# schem.net
KiCad netlist of a schematic drawn in EAGLE
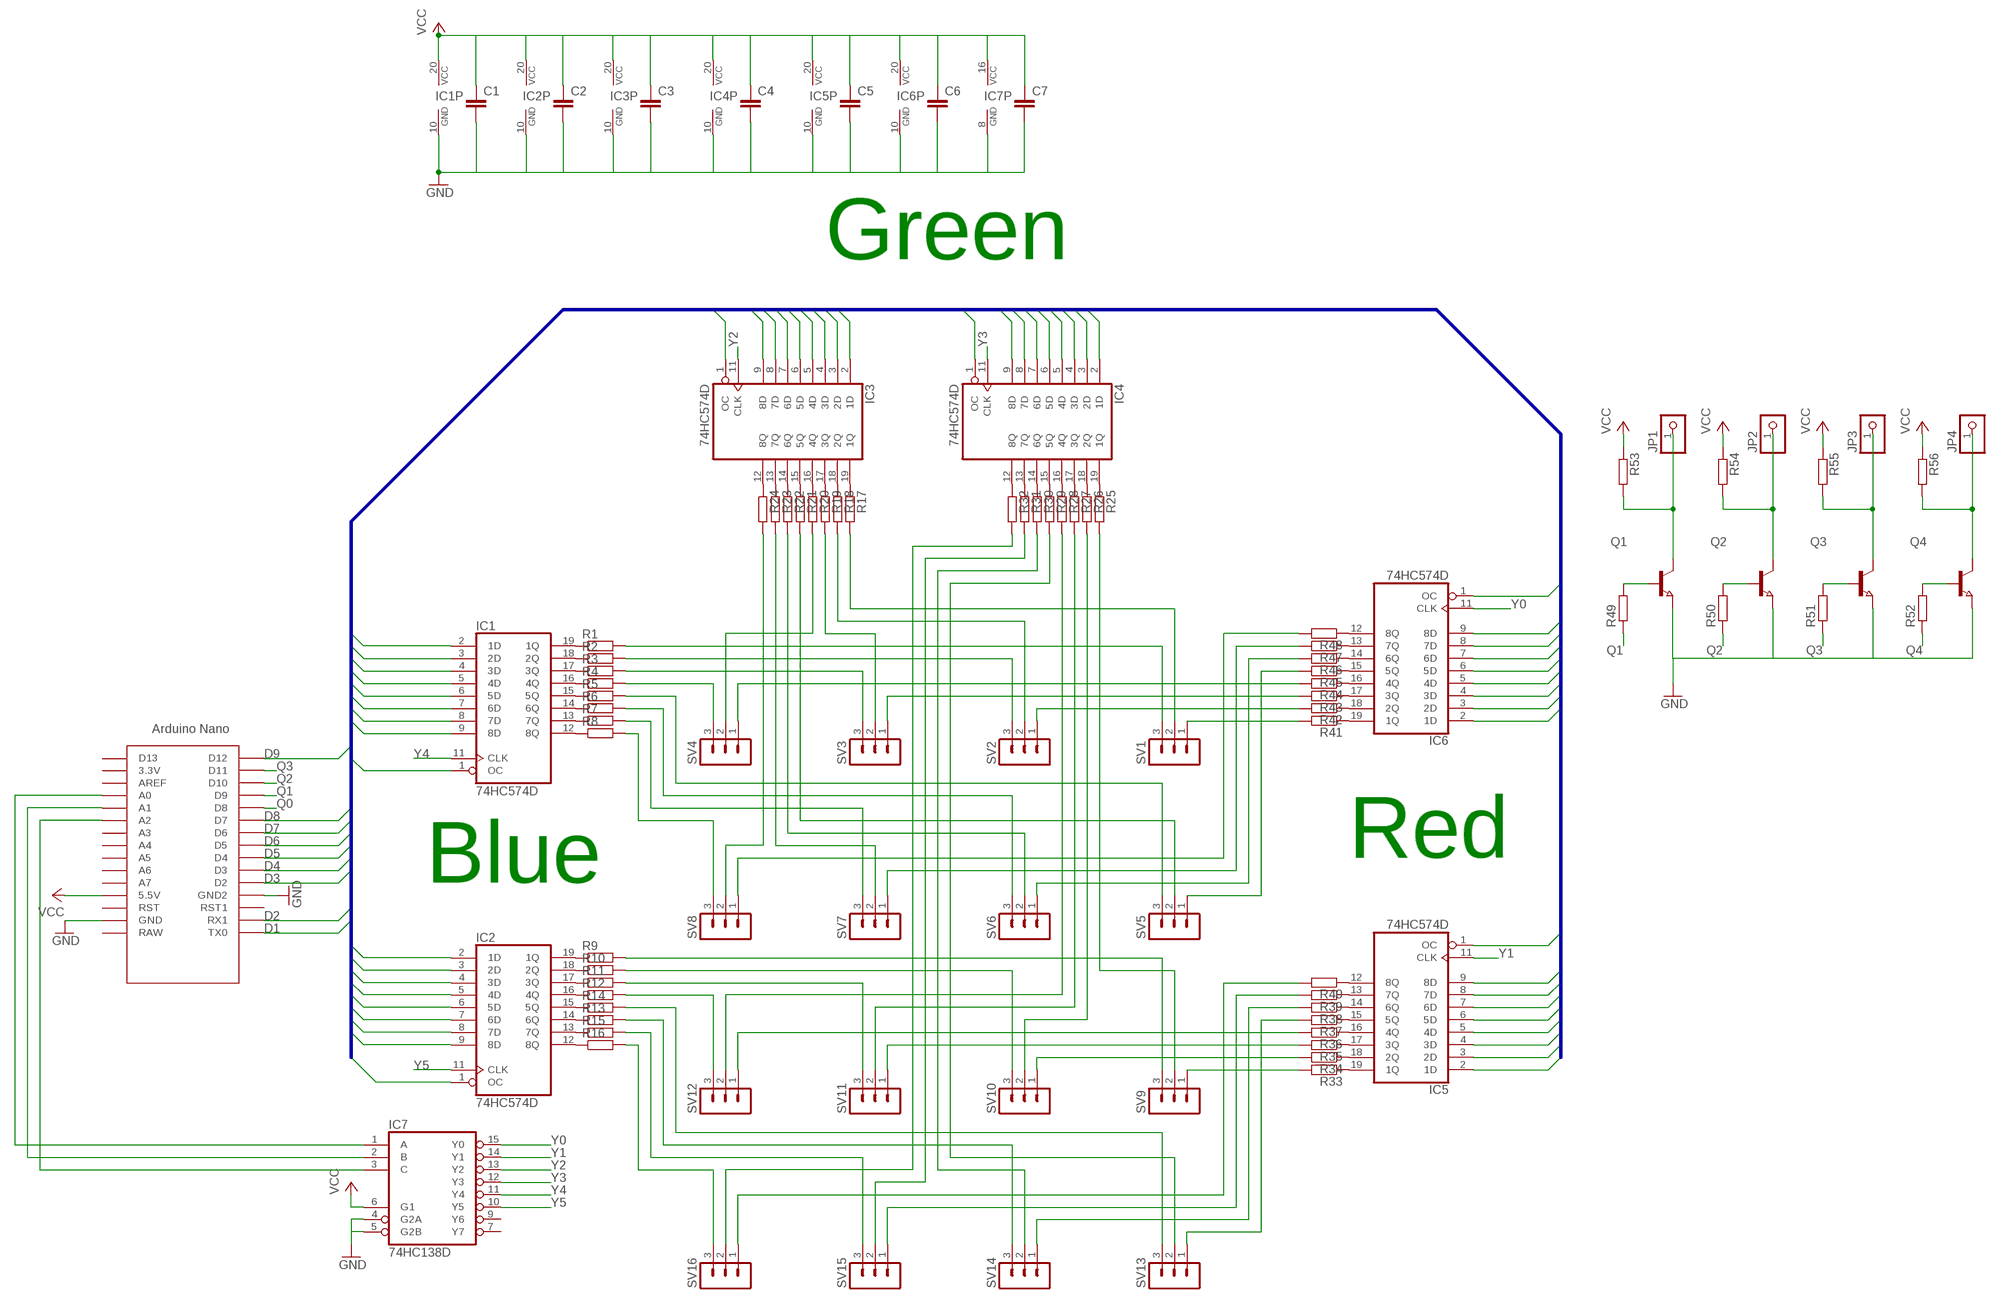
[diagram p0: schematic, sheet 1]

(export (version "E")
  (design (tool "Eeschema 10.0.6"))
  (components
    (comp (ref "C1")
      (value "C-EUC0805")
      (footprint "eagle-import:C0805")
      (libsource (lib "eagle-import") (part "C-EUC0805"))
    )
    (comp (ref "C2")
      (value "C-EUC0805")
      (footprint "eagle-import:C0805")
      (libsource (lib "eagle-import") (part "C-EUC0805"))
    )
    (comp (ref "C3")
      (value "C-EUC0805")
      (footprint "eagle-import:C0805")
      (libsource (lib "eagle-import") (part "C-EUC0805"))
    )
    (comp (ref "C4")
      (value "C-EUC0805")
      (footprint "eagle-import:C0805")
      (libsource (lib "eagle-import") (part "C-EUC0805"))
    )
    (comp (ref "C5")
      (value "C-EUC0805")
      (footprint "eagle-import:C0805")
      (libsource (lib "eagle-import") (part "C-EUC0805"))
    )
    (comp (ref "C6")
      (value "C-EUC0805")
      (footprint "eagle-import:C0805")
      (libsource (lib "eagle-import") (part "C-EUC0805"))
    )
    (comp (ref "C7")
      (value "C-EUC0805")
      (footprint "eagle-import:C0805")
      (libsource (lib "eagle-import") (part "C-EUC0805"))
    )
    (comp (ref "IC1")
      (value "74HC574D")
      (footprint "eagle-import:SO20W")
      (libsource (lib "eagle-import") (part "74574DHC"))
    )
    (comp (ref "IC2")
      (value "74HC574D")
      (footprint "eagle-import:SO20W")
      (libsource (lib "eagle-import") (part "74574DHC"))
    )
    (comp (ref "IC3")
      (value "74HC574D")
      (footprint "eagle-import:SO20W")
      (libsource (lib "eagle-import") (part "74574DHC"))
    )
    (comp (ref "IC4")
      (value "74HC574D")
      (footprint "eagle-import:SO20W")
      (libsource (lib "eagle-import") (part "74574DHC"))
    )
    (comp (ref "IC5")
      (value "74HC574D")
      (footprint "eagle-import:SO20W")
      (libsource (lib "eagle-import") (part "74574DHC"))
    )
    (comp (ref "IC6")
      (value "74HC574D")
      (footprint "eagle-import:SO20W")
      (libsource (lib "eagle-import") (part "74574DHC"))
    )
    (comp (ref "IC7")
      (value "74HC138D")
      (footprint "eagle-import:SO16")
      (libsource (lib "eagle-import") (part "74138DHC"))
    )
    (comp (ref "JP1")
      (value "PINHD-1X1")
      (footprint "eagle-import:1X01")
      (libsource (lib "eagle-import") (part "PINHD-1X1"))
    )
    (comp (ref "JP2")
      (value "PINHD-1X1")
      (footprint "eagle-import:1X01")
      (libsource (lib "eagle-import") (part "PINHD-1X1"))
    )
    (comp (ref "JP3")
      (value "PINHD-1X1")
      (footprint "eagle-import:1X01")
      (libsource (lib "eagle-import") (part "PINHD-1X1"))
    )
    (comp (ref "JP4")
      (value "PINHD-1X1")
      (footprint "eagle-import:1X01")
      (libsource (lib "eagle-import") (part "PINHD-1X1"))
    )
    (comp (ref "Q1")
      (value "NPN-TRANSISTOR_SOT23")
      (footprint "eagle-import:SOT23")
      (libsource (lib "eagle-import") (part "NPN-TRANSISTOR_SOT23"))
    )
    (comp (ref "Q2")
      (value "NPN-TRANSISTOR_SOT23")
      (footprint "eagle-import:SOT23")
      (libsource (lib "eagle-import") (part "NPN-TRANSISTOR_SOT23"))
    )
    (comp (ref "Q3")
      (value "NPN-TRANSISTOR_SOT23")
      (footprint "eagle-import:SOT23")
      (libsource (lib "eagle-import") (part "NPN-TRANSISTOR_SOT23"))
    )
    (comp (ref "Q4")
      (value "NPN-TRANSISTOR_SOT23")
      (footprint "eagle-import:SOT23")
      (libsource (lib "eagle-import") (part "NPN-TRANSISTOR_SOT23"))
    )
    (comp (ref "R1")
      (value "R-EU_R0805")
      (footprint "eagle-import:R0805")
      (libsource (lib "eagle-import") (part "R-EU_R0805"))
    )
    (comp (ref "R2")
      (value "R-EU_R0805")
      (footprint "eagle-import:R0805")
      (libsource (lib "eagle-import") (part "R-EU_R0805"))
    )
    (comp (ref "R3")
      (value "R-EU_R0805")
      (footprint "eagle-import:R0805")
      (libsource (lib "eagle-import") (part "R-EU_R0805"))
    )
    (comp (ref "R4")
      (value "R-EU_R0805")
      (footprint "eagle-import:R0805")
      (libsource (lib "eagle-import") (part "R-EU_R0805"))
    )
    (comp (ref "R5")
      (value "R-EU_R0805")
      (footprint "eagle-import:R0805")
      (libsource (lib "eagle-import") (part "R-EU_R0805"))
    )
    (comp (ref "R6")
      (value "R-EU_R0805")
      (footprint "eagle-import:R0805")
      (libsource (lib "eagle-import") (part "R-EU_R0805"))
    )
    (comp (ref "R7")
      (value "R-EU_R0805")
      (footprint "eagle-import:R0805")
      (libsource (lib "eagle-import") (part "R-EU_R0805"))
    )
    (comp (ref "R8")
      (value "R-EU_R0805")
      (footprint "eagle-import:R0805")
      (libsource (lib "eagle-import") (part "R-EU_R0805"))
    )
    (comp (ref "R9")
      (value "R-EU_R0805")
      (footprint "eagle-import:R0805")
      (libsource (lib "eagle-import") (part "R-EU_R0805"))
    )
    (comp (ref "R10")
      (value "R-EU_R0805")
      (footprint "eagle-import:R0805")
      (libsource (lib "eagle-import") (part "R-EU_R0805"))
    )
    (comp (ref "R11")
      (value "R-EU_R0805")
      (footprint "eagle-import:R0805")
      (libsource (lib "eagle-import") (part "R-EU_R0805"))
    )
    (comp (ref "R12")
      (value "R-EU_R0805")
      (footprint "eagle-import:R0805")
      (libsource (lib "eagle-import") (part "R-EU_R0805"))
    )
    (comp (ref "R13")
      (value "R-EU_R0805")
      (footprint "eagle-import:R0805")
      (libsource (lib "eagle-import") (part "R-EU_R0805"))
    )
    (comp (ref "R14")
      (value "R-EU_R0805")
      (footprint "eagle-import:R0805")
      (libsource (lib "eagle-import") (part "R-EU_R0805"))
    )
    (comp (ref "R15")
      (value "R-EU_R0805")
      (footprint "eagle-import:R0805")
      (libsource (lib "eagle-import") (part "R-EU_R0805"))
    )
    (comp (ref "R16")
      (value "R-EU_R0805")
      (footprint "eagle-import:R0805")
      (libsource (lib "eagle-import") (part "R-EU_R0805"))
    )
    (comp (ref "R17")
      (value "R-EU_R0805")
      (footprint "eagle-import:R0805")
      (libsource (lib "eagle-import") (part "R-EU_R0805"))
    )
    (comp (ref "R18")
      (value "R-EU_R0805")
      (footprint "eagle-import:R0805")
      (libsource (lib "eagle-import") (part "R-EU_R0805"))
    )
    (comp (ref "R19")
      (value "R-EU_R0805")
      (footprint "eagle-import:R0805")
      (libsource (lib "eagle-import") (part "R-EU_R0805"))
    )
    (comp (ref "R20")
      (value "R-EU_R0805")
      (footprint "eagle-import:R0805")
      (libsource (lib "eagle-import") (part "R-EU_R0805"))
    )
    (comp (ref "R21")
      (value "R-EU_R0805")
      (footprint "eagle-import:R0805")
      (libsource (lib "eagle-import") (part "R-EU_R0805"))
    )
    (comp (ref "R22")
      (value "R-EU_R0805")
      (footprint "eagle-import:R0805")
      (libsource (lib "eagle-import") (part "R-EU_R0805"))
    )
    (comp (ref "R23")
      (value "R-EU_R0805")
      (footprint "eagle-import:R0805")
      (libsource (lib "eagle-import") (part "R-EU_R0805"))
    )
    (comp (ref "R24")
      (value "R-EU_R0805")
      (footprint "eagle-import:R0805")
      (libsource (lib "eagle-import") (part "R-EU_R0805"))
    )
    (comp (ref "R25")
      (value "R-EU_R0805")
      (footprint "eagle-import:R0805")
      (libsource (lib "eagle-import") (part "R-EU_R0805"))
    )
    (comp (ref "R26")
      (value "R-EU_R0805")
      (footprint "eagle-import:R0805")
      (libsource (lib "eagle-import") (part "R-EU_R0805"))
    )
    (comp (ref "R27")
      (value "R-EU_R0805")
      (footprint "eagle-import:R0805")
      (libsource (lib "eagle-import") (part "R-EU_R0805"))
    )
    (comp (ref "R28")
      (value "R-EU_R0805")
      (footprint "eagle-import:R0805")
      (libsource (lib "eagle-import") (part "R-EU_R0805"))
    )
    (comp (ref "R29")
      (value "R-EU_R0805")
      (footprint "eagle-import:R0805")
      (libsource (lib "eagle-import") (part "R-EU_R0805"))
    )
    (comp (ref "R30")
      (value "R-EU_R0805")
      (footprint "eagle-import:R0805")
      (libsource (lib "eagle-import") (part "R-EU_R0805"))
    )
    (comp (ref "R31")
      (value "R-EU_R0805")
      (footprint "eagle-import:R0805")
      (libsource (lib "eagle-import") (part "R-EU_R0805"))
    )
    (comp (ref "R32")
      (value "R-EU_R0805")
      (footprint "eagle-import:R0805")
      (libsource (lib "eagle-import") (part "R-EU_R0805"))
    )
    (comp (ref "R33")
      (value "R-EU_R0805")
      (footprint "eagle-import:R0805")
      (libsource (lib "eagle-import") (part "R-EU_R0805"))
    )
    (comp (ref "R34")
      (value "R-EU_R0805")
      (footprint "eagle-import:R0805")
      (libsource (lib "eagle-import") (part "R-EU_R0805"))
    )
    (comp (ref "R35")
      (value "R-EU_R0805")
      (footprint "eagle-import:R0805")
      (libsource (lib "eagle-import") (part "R-EU_R0805"))
    )
    (comp (ref "R36")
      (value "R-EU_R0805")
      (footprint "eagle-import:R0805")
      (libsource (lib "eagle-import") (part "R-EU_R0805"))
    )
    (comp (ref "R37")
      (value "R-EU_R0805")
      (footprint "eagle-import:R0805")
      (libsource (lib "eagle-import") (part "R-EU_R0805"))
    )
    (comp (ref "R38")
      (value "R-EU_R0805")
      (footprint "eagle-import:R0805")
      (libsource (lib "eagle-import") (part "R-EU_R0805"))
    )
    (comp (ref "R39")
      (value "R-EU_R0805")
      (footprint "eagle-import:R0805")
      (libsource (lib "eagle-import") (part "R-EU_R0805"))
    )
    (comp (ref "R40")
      (value "R-EU_R0805")
      (footprint "eagle-import:R0805")
      (libsource (lib "eagle-import") (part "R-EU_R0805"))
    )
    (comp (ref "R41")
      (value "R-EU_R0805")
      (footprint "eagle-import:R0805")
      (libsource (lib "eagle-import") (part "R-EU_R0805"))
    )
    (comp (ref "R42")
      (value "R-EU_R0805")
      (footprint "eagle-import:R0805")
      (libsource (lib "eagle-import") (part "R-EU_R0805"))
    )
    (comp (ref "R43")
      (value "R-EU_R0805")
      (footprint "eagle-import:R0805")
      (libsource (lib "eagle-import") (part "R-EU_R0805"))
    )
    (comp (ref "R44")
      (value "R-EU_R0805")
      (footprint "eagle-import:R0805")
      (libsource (lib "eagle-import") (part "R-EU_R0805"))
    )
    (comp (ref "R45")
      (value "R-EU_R0805")
      (footprint "eagle-import:R0805")
      (libsource (lib "eagle-import") (part "R-EU_R0805"))
    )
    (comp (ref "R46")
      (value "R-EU_R0805")
      (footprint "eagle-import:R0805")
      (libsource (lib "eagle-import") (part "R-EU_R0805"))
    )
    (comp (ref "R47")
      (value "R-EU_R0805")
      (footprint "eagle-import:R0805")
      (libsource (lib "eagle-import") (part "R-EU_R0805"))
    )
    (comp (ref "R48")
      (value "R-EU_R0805")
      (footprint "eagle-import:R0805")
      (libsource (lib "eagle-import") (part "R-EU_R0805"))
    )
    (comp (ref "R49")
      (value "R-EU_R0805")
      (footprint "eagle-import:R0805")
      (libsource (lib "eagle-import") (part "R-EU_R0805"))
    )
    (comp (ref "R50")
      (value "R-EU_R0805")
      (footprint "eagle-import:R0805")
      (libsource (lib "eagle-import") (part "R-EU_R0805"))
    )
    (comp (ref "R51")
      (value "R-EU_R0805")
      (footprint "eagle-import:R0805")
      (libsource (lib "eagle-import") (part "R-EU_R0805"))
    )
    (comp (ref "R52")
      (value "R-EU_R0805")
      (footprint "eagle-import:R0805")
      (libsource (lib "eagle-import") (part "R-EU_R0805"))
    )
    (comp (ref "R53")
      (value "R-EU_R0805")
      (footprint "eagle-import:R0805")
      (libsource (lib "eagle-import") (part "R-EU_R0805"))
    )
    (comp (ref "R54")
      (value "R-EU_R0805")
      (footprint "eagle-import:R0805")
      (libsource (lib "eagle-import") (part "R-EU_R0805"))
    )
    (comp (ref "R55")
      (value "R-EU_R0805")
      (footprint "eagle-import:R0805")
      (libsource (lib "eagle-import") (part "R-EU_R0805"))
    )
    (comp (ref "R56")
      (value "R-EU_R0805")
      (footprint "eagle-import:R0805")
      (libsource (lib "eagle-import") (part "R-EU_R0805"))
    )
    (comp (ref "SV1")
      (value "MA03-1")
      (footprint "eagle-import:MA03-1")
      (libsource (lib "eagle-import") (part "MA03-1"))
    )
    (comp (ref "SV2")
      (value "MA03-1")
      (footprint "eagle-import:MA03-1")
      (libsource (lib "eagle-import") (part "MA03-1"))
    )
    (comp (ref "SV3")
      (value "MA03-1")
      (footprint "eagle-import:MA03-1")
      (libsource (lib "eagle-import") (part "MA03-1"))
    )
    (comp (ref "SV4")
      (value "MA03-1")
      (footprint "eagle-import:MA03-1")
      (libsource (lib "eagle-import") (part "MA03-1"))
    )
    (comp (ref "SV5")
      (value "MA03-1")
      (footprint "eagle-import:MA03-1")
      (libsource (lib "eagle-import") (part "MA03-1"))
    )
    (comp (ref "SV6")
      (value "MA03-1")
      (footprint "eagle-import:MA03-1")
      (libsource (lib "eagle-import") (part "MA03-1"))
    )
    (comp (ref "SV7")
      (value "MA03-1")
      (footprint "eagle-import:MA03-1")
      (libsource (lib "eagle-import") (part "MA03-1"))
    )
    (comp (ref "SV8")
      (value "MA03-1")
      (footprint "eagle-import:MA03-1")
      (libsource (lib "eagle-import") (part "MA03-1"))
    )
    (comp (ref "SV9")
      (value "MA03-1")
      (footprint "eagle-import:MA03-1")
      (libsource (lib "eagle-import") (part "MA03-1"))
    )
    (comp (ref "SV10")
      (value "MA03-1")
      (footprint "eagle-import:MA03-1")
      (libsource (lib "eagle-import") (part "MA03-1"))
    )
    (comp (ref "SV11")
      (value "MA03-1")
      (footprint "eagle-import:MA03-1")
      (libsource (lib "eagle-import") (part "MA03-1"))
    )
    (comp (ref "SV12")
      (value "MA03-1")
      (footprint "eagle-import:MA03-1")
      (libsource (lib "eagle-import") (part "MA03-1"))
    )
    (comp (ref "SV13")
      (value "MA03-1")
      (footprint "eagle-import:MA03-1")
      (libsource (lib "eagle-import") (part "MA03-1"))
    )
    (comp (ref "SV14")
      (value "MA03-1")
      (footprint "eagle-import:MA03-1")
      (libsource (lib "eagle-import") (part "MA03-1"))
    )
    (comp (ref "SV15")
      (value "MA03-1")
      (footprint "eagle-import:MA03-1")
      (libsource (lib "eagle-import") (part "MA03-1"))
    )
    (comp (ref "SV16")
      (value "MA03-1")
      (footprint "eagle-import:MA03-1")
      (libsource (lib "eagle-import") (part "MA03-1"))
    )
    (comp (ref "U$1")
      (value "NANO")
      (footprint "eagle-import:NANO")
      (libsource (lib "eagle-import") (part "NANO"))
    )
  )
  (nets
    (net (code "1") (name "/D1") (class "Default")
      (node (ref "IC1") (pin "2") (pinfunction "1D_2") (pintype "input"))
      (node (ref "IC2") (pin "2") (pinfunction "1D_2") (pintype "input"))
      (node (ref "IC3") (pin "2") (pinfunction "1D_2") (pintype "input"))
      (node (ref "IC4") (pin "2") (pinfunction "1D_2") (pintype "input"))
      (node (ref "IC5") (pin "2") (pinfunction "1D_2") (pintype "input"))
      (node (ref "IC6") (pin "2") (pinfunction "1D_2") (pintype "input"))
      (node (ref "U$1") (pin "TX0") (pinfunction "TX0_TX0") (pintype "bidirectional"))
    )
    (net (code "2") (name "/D2") (class "Default")
      (node (ref "IC1") (pin "3") (pinfunction "2D_3") (pintype "input"))
      (node (ref "IC2") (pin "3") (pinfunction "2D_3") (pintype "input"))
      (node (ref "IC3") (pin "3") (pinfunction "2D_3") (pintype "input"))
      (node (ref "IC4") (pin "3") (pinfunction "2D_3") (pintype "input"))
      (node (ref "IC5") (pin "3") (pinfunction "2D_3") (pintype "input"))
      (node (ref "IC6") (pin "3") (pinfunction "2D_3") (pintype "input"))
      (node (ref "U$1") (pin "RX1") (pinfunction "RX1_RX1") (pintype "bidirectional"))
    )
    (net (code "3") (name "/D3") (class "Default")
      (node (ref "IC1") (pin "4") (pinfunction "3D_4") (pintype "input"))
      (node (ref "IC2") (pin "4") (pinfunction "3D_4") (pintype "input"))
      (node (ref "IC3") (pin "4") (pinfunction "3D_4") (pintype "input"))
      (node (ref "IC4") (pin "4") (pinfunction "3D_4") (pintype "input"))
      (node (ref "IC5") (pin "4") (pinfunction "3D_4") (pintype "input"))
      (node (ref "IC6") (pin "4") (pinfunction "3D_4") (pintype "input"))
      (node (ref "U$1") (pin "D2") (pinfunction "D2_D2") (pintype "bidirectional"))
    )
    (net (code "4") (name "/D4") (class "Default")
      (node (ref "IC1") (pin "5") (pinfunction "4D_5") (pintype "input"))
      (node (ref "IC2") (pin "5") (pinfunction "4D_5") (pintype "input"))
      (node (ref "IC3") (pin "5") (pinfunction "4D_5") (pintype "input"))
      (node (ref "IC4") (pin "5") (pinfunction "4D_5") (pintype "input"))
      (node (ref "IC5") (pin "5") (pinfunction "4D_5") (pintype "input"))
      (node (ref "IC6") (pin "5") (pinfunction "4D_5") (pintype "input"))
      (node (ref "U$1") (pin "D3") (pinfunction "D3_D3") (pintype "bidirectional"))
    )
    (net (code "5") (name "/D5") (class "Default")
      (node (ref "IC1") (pin "6") (pinfunction "5D_6") (pintype "input"))
      (node (ref "IC2") (pin "6") (pinfunction "5D_6") (pintype "input"))
      (node (ref "IC3") (pin "6") (pinfunction "5D_6") (pintype "input"))
      (node (ref "IC4") (pin "6") (pinfunction "5D_6") (pintype "input"))
      (node (ref "IC5") (pin "6") (pinfunction "5D_6") (pintype "input"))
      (node (ref "IC6") (pin "6") (pinfunction "5D_6") (pintype "input"))
      (node (ref "U$1") (pin "D4") (pinfunction "D4_D4") (pintype "bidirectional"))
    )
    (net (code "6") (name "/D6") (class "Default")
      (node (ref "IC1") (pin "7") (pinfunction "6D_7") (pintype "input"))
      (node (ref "IC2") (pin "7") (pinfunction "6D_7") (pintype "input"))
      (node (ref "IC3") (pin "7") (pinfunction "6D_7") (pintype "input"))
      (node (ref "IC4") (pin "7") (pinfunction "6D_7") (pintype "input"))
      (node (ref "IC5") (pin "7") (pinfunction "6D_7") (pintype "input"))
      (node (ref "IC6") (pin "7") (pinfunction "6D_7") (pintype "input"))
      (node (ref "U$1") (pin "D5") (pinfunction "D5_D5") (pintype "bidirectional"))
    )
    (net (code "7") (name "/D7") (class "Default")
      (node (ref "IC1") (pin "8") (pinfunction "7D_8") (pintype "input"))
      (node (ref "IC2") (pin "8") (pinfunction "7D_8") (pintype "input"))
      (node (ref "IC3") (pin "8") (pinfunction "7D_8") (pintype "input"))
      (node (ref "IC4") (pin "8") (pinfunction "7D_8") (pintype "input"))
      (node (ref "IC5") (pin "8") (pinfunction "7D_8") (pintype "input"))
      (node (ref "IC6") (pin "8") (pinfunction "7D_8") (pintype "input"))
      (node (ref "U$1") (pin "D6") (pinfunction "D6_D6") (pintype "bidirectional"))
    )
    (net (code "8") (name "/D8") (class "Default")
      (node (ref "IC1") (pin "9") (pinfunction "8D_9") (pintype "input"))
      (node (ref "IC2") (pin "9") (pinfunction "8D_9") (pintype "input"))
      (node (ref "IC3") (pin "9") (pinfunction "8D_9") (pintype "input"))
      (node (ref "IC4") (pin "9") (pinfunction "8D_9") (pintype "input"))
      (node (ref "IC5") (pin "9") (pinfunction "8D_9") (pintype "input"))
      (node (ref "IC6") (pin "9") (pinfunction "8D_9") (pintype "input"))
      (node (ref "U$1") (pin "D7") (pinfunction "D7_D7") (pintype "bidirectional"))
    )
    (net (code "9") (name "/D9") (class "Default")
      (node (ref "IC1") (pin "1") (pinfunction "OC_1") (pintype "input"))
      (node (ref "IC2") (pin "1") (pinfunction "OC_1") (pintype "input"))
      (node (ref "IC3") (pin "1") (pinfunction "OC_1") (pintype "input"))
      (node (ref "IC4") (pin "1") (pinfunction "OC_1") (pintype "input"))
      (node (ref "IC5") (pin "1") (pinfunction "OC_1") (pintype "input"))
      (node (ref "IC6") (pin "1") (pinfunction "OC_1") (pintype "input"))
      (node (ref "U$1") (pin "D12") (pinfunction "D12_D12") (pintype "bidirectional"))
    )
    (net (code "10") (name "/Q0") (class "Default")
      (node (ref "U$1") (pin "D8") (pinfunction "D8_D8") (pintype "bidirectional"))
    )
    (net (code "11") (name "/Q1") (class "Default")
      (node (ref "R49") (pin "1") (pinfunction "1_1") (pintype "passive"))
      (node (ref "U$1") (pin "D9") (pinfunction "D9_D9") (pintype "bidirectional"))
    )
    (net (code "12") (name "/Q2") (class "Default")
      (node (ref "R50") (pin "1") (pinfunction "1_1") (pintype "passive"))
      (node (ref "U$1") (pin "D10") (pinfunction "D10_D10") (pintype "bidirectional"))
    )
    (net (code "13") (name "/Q3") (class "Default")
      (node (ref "R51") (pin "1") (pinfunction "1_1") (pintype "passive"))
      (node (ref "U$1") (pin "D11") (pinfunction "D11_D11") (pintype "bidirectional"))
    )
    (net (code "14") (name "/Q4") (class "Default")
      (node (ref "R52") (pin "1") (pinfunction "1_1") (pintype "passive"))
    )
    (net (code "15") (name "/Y0") (class "Default")
      (node (ref "IC6") (pin "11") (pinfunction "CLK_11") (pintype "input"))
      (node (ref "IC7") (pin "15") (pinfunction "Y0_15") (pintype "output"))
    )
    (net (code "16") (name "/Y1") (class "Default")
      (node (ref "IC5") (pin "11") (pinfunction "CLK_11") (pintype "input"))
      (node (ref "IC7") (pin "14") (pinfunction "Y1_14") (pintype "output"))
    )
    (net (code "17") (name "/Y2") (class "Default")
      (node (ref "IC3") (pin "11") (pinfunction "CLK_11") (pintype "input"))
      (node (ref "IC7") (pin "13") (pinfunction "Y2_13") (pintype "output"))
    )
    (net (code "18") (name "/Y3") (class "Default")
      (node (ref "IC4") (pin "11") (pinfunction "CLK_11") (pintype "input"))
      (node (ref "IC7") (pin "12") (pinfunction "Y3_12") (pintype "output"))
    )
    (net (code "19") (name "/Y4") (class "Default")
      (node (ref "IC1") (pin "11") (pinfunction "CLK_11") (pintype "input"))
      (node (ref "IC7") (pin "11") (pinfunction "Y4_11") (pintype "output"))
    )
    (net (code "20") (name "/Y5") (class "Default")
      (node (ref "IC2") (pin "11") (pinfunction "CLK_11") (pintype "input"))
      (node (ref "IC7") (pin "10") (pinfunction "Y5_10") (pintype "output"))
    )
    (net (code "21") (name "GND") (class "Default")
      (node (ref "C1") (pin "2") (pinfunction "2_2") (pintype "passive"))
      (node (ref "C2") (pin "2") (pinfunction "2_2") (pintype "passive"))
      (node (ref "C3") (pin "2") (pinfunction "2_2") (pintype "passive"))
      (node (ref "C4") (pin "2") (pinfunction "2_2") (pintype "passive"))
      (node (ref "C5") (pin "2") (pinfunction "2_2") (pintype "passive"))
      (node (ref "C6") (pin "2") (pinfunction "2_2") (pintype "passive"))
      (node (ref "C7") (pin "2") (pinfunction "2_2") (pintype "passive"))
      (node (ref "IC1") (pin "10") (pinfunction "GND_10") (pintype "power_in"))
      (node (ref "IC2") (pin "10") (pinfunction "GND_10") (pintype "power_in"))
      (node (ref "IC3") (pin "10") (pinfunction "GND_10") (pintype "power_in"))
      (node (ref "IC4") (pin "10") (pinfunction "GND_10") (pintype "power_in"))
      (node (ref "IC5") (pin "10") (pinfunction "GND_10") (pintype "power_in"))
      (node (ref "IC6") (pin "10") (pinfunction "GND_10") (pintype "power_in"))
      (node (ref "IC7") (pin "4") (pinfunction "G2A_4") (pintype "input"))
      (node (ref "IC7") (pin "5") (pinfunction "G2B_5") (pintype "input"))
      (node (ref "IC7") (pin "8") (pinfunction "GND_8") (pintype "power_in"))
      (node (ref "Q1") (pin "2") (pinfunction "E_2") (pintype "passive"))
      (node (ref "Q2") (pin "2") (pinfunction "E_2") (pintype "passive"))
      (node (ref "Q3") (pin "2") (pinfunction "E_2") (pintype "passive"))
      (node (ref "Q4") (pin "2") (pinfunction "E_2") (pintype "passive"))
      (node (ref "U$1") (pin "GND") (pinfunction "GND_GND") (pintype "bidirectional"))
      (node (ref "U$1") (pin "GND1") (pinfunction "GND2_GND1") (pintype "bidirectional"))
    )
    (net (code "22") (name "Net-(IC1A-1Q)") (class "Default")
      (node (ref "IC1") (pin "19") (pinfunction "1Q_19") (pintype "tri_state"))
      (node (ref "R1") (pin "1") (pinfunction "1_1") (pintype "passive"))
    )
    (net (code "23") (name "Net-(IC1A-2Q)") (class "Default")
      (node (ref "IC1") (pin "18") (pinfunction "2Q_18") (pintype "tri_state"))
      (node (ref "R2") (pin "1") (pinfunction "1_1") (pintype "passive"))
    )
    (net (code "24") (name "Net-(IC1A-3Q)") (class "Default")
      (node (ref "IC1") (pin "17") (pinfunction "3Q_17") (pintype "tri_state"))
      (node (ref "R3") (pin "1") (pinfunction "1_1") (pintype "passive"))
    )
    (net (code "25") (name "Net-(IC1A-4Q)") (class "Default")
      (node (ref "IC1") (pin "16") (pinfunction "4Q_16") (pintype "tri_state"))
      (node (ref "R4") (pin "1") (pinfunction "1_1") (pintype "passive"))
    )
    (net (code "26") (name "Net-(IC1A-5Q)") (class "Default")
      (node (ref "IC1") (pin "15") (pinfunction "5Q_15") (pintype "tri_state"))
      (node (ref "R5") (pin "1") (pinfunction "1_1") (pintype "passive"))
    )
    (net (code "27") (name "Net-(IC1A-6Q)") (class "Default")
      (node (ref "IC1") (pin "14") (pinfunction "6Q_14") (pintype "tri_state"))
      (node (ref "R6") (pin "1") (pinfunction "1_1") (pintype "passive"))
    )
    (net (code "28") (name "Net-(IC1A-7Q)") (class "Default")
      (node (ref "IC1") (pin "13") (pinfunction "7Q_13") (pintype "tri_state"))
      (node (ref "R7") (pin "1") (pinfunction "1_1") (pintype "passive"))
    )
    (net (code "29") (name "Net-(IC1A-8Q)") (class "Default")
      (node (ref "IC1") (pin "12") (pinfunction "8Q_12") (pintype "tri_state"))
      (node (ref "R8") (pin "1") (pinfunction "1_1") (pintype "passive"))
    )
    (net (code "30") (name "Net-(IC2A-1Q)") (class "Default")
      (node (ref "IC2") (pin "19") (pinfunction "1Q_19") (pintype "tri_state"))
      (node (ref "R9") (pin "1") (pinfunction "1_1") (pintype "passive"))
    )
    (net (code "31") (name "Net-(IC2A-2Q)") (class "Default")
      (node (ref "IC2") (pin "18") (pinfunction "2Q_18") (pintype "tri_state"))
      (node (ref "R10") (pin "1") (pinfunction "1_1") (pintype "passive"))
    )
    (net (code "32") (name "Net-(IC2A-3Q)") (class "Default")
      (node (ref "IC2") (pin "17") (pinfunction "3Q_17") (pintype "tri_state"))
      (node (ref "R11") (pin "1") (pinfunction "1_1") (pintype "passive"))
    )
    (net (code "33") (name "Net-(IC2A-4Q)") (class "Default")
      (node (ref "IC2") (pin "16") (pinfunction "4Q_16") (pintype "tri_state"))
      (node (ref "R12") (pin "1") (pinfunction "1_1") (pintype "passive"))
    )
    (net (code "34") (name "Net-(IC2A-5Q)") (class "Default")
      (node (ref "IC2") (pin "15") (pinfunction "5Q_15") (pintype "tri_state"))
      (node (ref "R14") (pin "1") (pinfunction "1_1") (pintype "passive"))
    )
    (net (code "35") (name "Net-(IC2A-6Q)") (class "Default")
      (node (ref "IC2") (pin "14") (pinfunction "6Q_14") (pintype "tri_state"))
      (node (ref "R13") (pin "1") (pinfunction "1_1") (pintype "passive"))
    )
    (net (code "36") (name "Net-(IC2A-7Q)") (class "Default")
      (node (ref "IC2") (pin "13") (pinfunction "7Q_13") (pintype "tri_state"))
      (node (ref "R15") (pin "1") (pinfunction "1_1") (pintype "passive"))
    )
    (net (code "37") (name "Net-(IC2A-8Q)") (class "Default")
      (node (ref "IC2") (pin "12") (pinfunction "8Q_12") (pintype "tri_state"))
      (node (ref "R16") (pin "1") (pinfunction "1_1") (pintype "passive"))
    )
    (net (code "38") (name "Net-(IC3A-1Q)") (class "Default")
      (node (ref "IC3") (pin "19") (pinfunction "1Q_19") (pintype "tri_state"))
      (node (ref "R17") (pin "1") (pinfunction "1_1") (pintype "passive"))
    )
    (net (code "39") (name "Net-(IC3A-2Q)") (class "Default")
      (node (ref "IC3") (pin "18") (pinfunction "2Q_18") (pintype "tri_state"))
      (node (ref "R18") (pin "1") (pinfunction "1_1") (pintype "passive"))
    )
    (net (code "40") (name "Net-(IC3A-3Q)") (class "Default")
      (node (ref "IC3") (pin "17") (pinfunction "3Q_17") (pintype "tri_state"))
      (node (ref "R19") (pin "1") (pinfunction "1_1") (pintype "passive"))
    )
    (net (code "41") (name "Net-(IC3A-4Q)") (class "Default")
      (node (ref "IC3") (pin "16") (pinfunction "4Q_16") (pintype "tri_state"))
      (node (ref "R20") (pin "1") (pinfunction "1_1") (pintype "passive"))
    )
    (net (code "42") (name "Net-(IC3A-5Q)") (class "Default")
      (node (ref "IC3") (pin "15") (pinfunction "5Q_15") (pintype "tri_state"))
      (node (ref "R21") (pin "1") (pinfunction "1_1") (pintype "passive"))
    )
    (net (code "43") (name "Net-(IC3A-6Q)") (class "Default")
      (node (ref "IC3") (pin "14") (pinfunction "6Q_14") (pintype "tri_state"))
      (node (ref "R22") (pin "1") (pinfunction "1_1") (pintype "passive"))
    )
    (net (code "44") (name "Net-(IC3A-7Q)") (class "Default")
      (node (ref "IC3") (pin "13") (pinfunction "7Q_13") (pintype "tri_state"))
      (node (ref "R23") (pin "1") (pinfunction "1_1") (pintype "passive"))
    )
    (net (code "45") (name "Net-(IC3A-8Q)") (class "Default")
      (node (ref "IC3") (pin "12") (pinfunction "8Q_12") (pintype "tri_state"))
      (node (ref "R24") (pin "1") (pinfunction "1_1") (pintype "passive"))
    )
    (net (code "46") (name "Net-(IC4A-1Q)") (class "Default")
      (node (ref "IC4") (pin "19") (pinfunction "1Q_19") (pintype "tri_state"))
      (node (ref "R25") (pin "1") (pinfunction "1_1") (pintype "passive"))
    )
    (net (code "47") (name "Net-(IC4A-2Q)") (class "Default")
      (node (ref "IC4") (pin "18") (pinfunction "2Q_18") (pintype "tri_state"))
      (node (ref "R26") (pin "1") (pinfunction "1_1") (pintype "passive"))
    )
    (net (code "48") (name "Net-(IC4A-3Q)") (class "Default")
      (node (ref "IC4") (pin "17") (pinfunction "3Q_17") (pintype "tri_state"))
      (node (ref "R27") (pin "1") (pinfunction "1_1") (pintype "passive"))
    )
    (net (code "49") (name "Net-(IC4A-4Q)") (class "Default")
      (node (ref "IC4") (pin "16") (pinfunction "4Q_16") (pintype "tri_state"))
      (node (ref "R28") (pin "1") (pinfunction "1_1") (pintype "passive"))
    )
    (net (code "50") (name "Net-(IC4A-5Q)") (class "Default")
      (node (ref "IC4") (pin "15") (pinfunction "5Q_15") (pintype "tri_state"))
      (node (ref "R29") (pin "1") (pinfunction "1_1") (pintype "passive"))
    )
    (net (code "51") (name "Net-(IC4A-6Q)") (class "Default")
      (node (ref "IC4") (pin "14") (pinfunction "6Q_14") (pintype "tri_state"))
      (node (ref "R30") (pin "1") (pinfunction "1_1") (pintype "passive"))
    )
    (net (code "52") (name "Net-(IC4A-7Q)") (class "Default")
      (node (ref "IC4") (pin "13") (pinfunction "7Q_13") (pintype "tri_state"))
      (node (ref "R31") (pin "1") (pinfunction "1_1") (pintype "passive"))
    )
    (net (code "53") (name "Net-(IC4A-8Q)") (class "Default")
      (node (ref "IC4") (pin "12") (pinfunction "8Q_12") (pintype "tri_state"))
      (node (ref "R32") (pin "1") (pinfunction "1_1") (pintype "passive"))
    )
    (net (code "54") (name "Net-(IC5A-1Q)") (class "Default")
      (node (ref "IC5") (pin "19") (pinfunction "1Q_19") (pintype "tri_state"))
      (node (ref "R33") (pin "1") (pinfunction "1_1") (pintype "passive"))
    )
    (net (code "55") (name "Net-(IC5A-2Q)") (class "Default")
      (node (ref "IC5") (pin "18") (pinfunction "2Q_18") (pintype "tri_state"))
      (node (ref "R34") (pin "1") (pinfunction "1_1") (pintype "passive"))
    )
    (net (code "56") (name "Net-(IC5A-3Q)") (class "Default")
      (node (ref "IC5") (pin "17") (pinfunction "3Q_17") (pintype "tri_state"))
      (node (ref "R35") (pin "1") (pinfunction "1_1") (pintype "passive"))
    )
    (net (code "57") (name "Net-(IC5A-4Q)") (class "Default")
      (node (ref "IC5") (pin "16") (pinfunction "4Q_16") (pintype "tri_state"))
      (node (ref "R36") (pin "1") (pinfunction "1_1") (pintype "passive"))
    )
    (net (code "58") (name "Net-(IC5A-5Q)") (class "Default")
      (node (ref "IC5") (pin "15") (pinfunction "5Q_15") (pintype "tri_state"))
      (node (ref "R37") (pin "1") (pinfunction "1_1") (pintype "passive"))
    )
    (net (code "59") (name "Net-(IC5A-6Q)") (class "Default")
      (node (ref "IC5") (pin "14") (pinfunction "6Q_14") (pintype "tri_state"))
      (node (ref "R38") (pin "1") (pinfunction "1_1") (pintype "passive"))
    )
    (net (code "60") (name "Net-(IC5A-7Q)") (class "Default")
      (node (ref "IC5") (pin "13") (pinfunction "7Q_13") (pintype "tri_state"))
      (node (ref "R39") (pin "1") (pinfunction "1_1") (pintype "passive"))
    )
    (net (code "61") (name "Net-(IC5A-8Q)") (class "Default")
      (node (ref "IC5") (pin "12") (pinfunction "8Q_12") (pintype "tri_state"))
      (node (ref "R40") (pin "1") (pinfunction "1_1") (pintype "passive"))
    )
    (net (code "62") (name "Net-(IC6A-1Q)") (class "Default")
      (node (ref "IC6") (pin "19") (pinfunction "1Q_19") (pintype "tri_state"))
      (node (ref "R41") (pin "1") (pinfunction "1_1") (pintype "passive"))
    )
    (net (code "63") (name "Net-(IC6A-2Q)") (class "Default")
      (node (ref "IC6") (pin "18") (pinfunction "2Q_18") (pintype "tri_state"))
      (node (ref "R42") (pin "1") (pinfunction "1_1") (pintype "passive"))
    )
    (net (code "64") (name "Net-(IC6A-3Q)") (class "Default")
      (node (ref "IC6") (pin "17") (pinfunction "3Q_17") (pintype "tri_state"))
      (node (ref "R43") (pin "1") (pinfunction "1_1") (pintype "passive"))
    )
    (net (code "65") (name "Net-(IC6A-4Q)") (class "Default")
      (node (ref "IC6") (pin "16") (pinfunction "4Q_16") (pintype "tri_state"))
      (node (ref "R44") (pin "1") (pinfunction "1_1") (pintype "passive"))
    )
    (net (code "66") (name "Net-(IC6A-5Q)") (class "Default")
      (node (ref "IC6") (pin "15") (pinfunction "5Q_15") (pintype "tri_state"))
      (node (ref "R45") (pin "1") (pinfunction "1_1") (pintype "passive"))
    )
    (net (code "67") (name "Net-(IC6A-6Q)") (class "Default")
      (node (ref "IC6") (pin "14") (pinfunction "6Q_14") (pintype "tri_state"))
      (node (ref "R46") (pin "1") (pinfunction "1_1") (pintype "passive"))
    )
    (net (code "68") (name "Net-(IC6A-7Q)") (class "Default")
      (node (ref "IC6") (pin "13") (pinfunction "7Q_13") (pintype "tri_state"))
      (node (ref "R47") (pin "1") (pinfunction "1_1") (pintype "passive"))
    )
    (net (code "69") (name "Net-(IC6A-8Q)") (class "Default")
      (node (ref "IC6") (pin "12") (pinfunction "8Q_12") (pintype "tri_state"))
      (node (ref "R48") (pin "1") (pinfunction "1_1") (pintype "passive"))
    )
    (net (code "70") (name "Net-(IC7A-A)") (class "Default")
      (node (ref "IC7") (pin "1") (pinfunction "A_1") (pintype "input"))
      (node (ref "U$1") (pin "A0") (pinfunction "A0_A0") (pintype "bidirectional"))
    )
    (net (code "71") (name "Net-(IC7A-B)") (class "Default")
      (node (ref "IC7") (pin "2") (pinfunction "B_2") (pintype "input"))
      (node (ref "U$1") (pin "A1") (pinfunction "A1_A1") (pintype "bidirectional"))
    )
    (net (code "72") (name "Net-(IC7A-C)") (class "Default")
      (node (ref "IC7") (pin "3") (pinfunction "C_3") (pintype "input"))
      (node (ref "U$1") (pin "A2") (pinfunction "A2_A2") (pintype "bidirectional"))
    )
    (net (code "73") (name "Net-(Q1-B)") (class "Default")
      (node (ref "Q1") (pin "1") (pinfunction "B_1") (pintype "passive"))
      (node (ref "R49") (pin "2") (pinfunction "2_2") (pintype "passive"))
    )
    (net (code "74") (name "Net-(Q1-C)") (class "Default")
      (node (ref "JP1") (pin "1") (pinfunction "1_1") (pintype "passive"))
      (node (ref "Q1") (pin "3") (pinfunction "C_3") (pintype "passive"))
      (node (ref "R53") (pin "2") (pinfunction "2_2") (pintype "passive"))
    )
    (net (code "75") (name "Net-(Q2-B)") (class "Default")
      (node (ref "Q2") (pin "1") (pinfunction "B_1") (pintype "passive"))
      (node (ref "R50") (pin "2") (pinfunction "2_2") (pintype "passive"))
    )
    (net (code "76") (name "Net-(Q2-C)") (class "Default")
      (node (ref "JP2") (pin "1") (pinfunction "1_1") (pintype "passive"))
      (node (ref "Q2") (pin "3") (pinfunction "C_3") (pintype "passive"))
      (node (ref "R54") (pin "2") (pinfunction "2_2") (pintype "passive"))
    )
    (net (code "77") (name "Net-(Q3-B)") (class "Default")
      (node (ref "Q3") (pin "1") (pinfunction "B_1") (pintype "passive"))
      (node (ref "R51") (pin "2") (pinfunction "2_2") (pintype "passive"))
    )
    (net (code "78") (name "Net-(Q3-C)") (class "Default")
      (node (ref "JP3") (pin "1") (pinfunction "1_1") (pintype "passive"))
      (node (ref "Q3") (pin "3") (pinfunction "C_3") (pintype "passive"))
      (node (ref "R55") (pin "2") (pinfunction "2_2") (pintype "passive"))
    )
    (net (code "79") (name "Net-(Q4-B)") (class "Default")
      (node (ref "Q4") (pin "1") (pinfunction "B_1") (pintype "passive"))
      (node (ref "R52") (pin "2") (pinfunction "2_2") (pintype "passive"))
    )
    (net (code "80") (name "Net-(Q4-C)") (class "Default")
      (node (ref "JP4") (pin "1") (pinfunction "1_1") (pintype "passive"))
      (node (ref "Q4") (pin "3") (pinfunction "C_3") (pintype "passive"))
      (node (ref "R56") (pin "2") (pinfunction "2_2") (pintype "passive"))
    )
    (net (code "81") (name "Net-(R1-Pad2)") (class "Default")
      (node (ref "R1") (pin "2") (pinfunction "2_2") (pintype "passive"))
      (node (ref "SV1") (pin "3") (pinfunction "3_3") (pintype "passive"))
    )
    (net (code "82") (name "Net-(R2-Pad2)") (class "Default")
      (node (ref "R2") (pin "2") (pinfunction "2_2") (pintype "passive"))
      (node (ref "SV2") (pin "3") (pinfunction "3_3") (pintype "passive"))
    )
    (net (code "83") (name "Net-(R3-Pad2)") (class "Default")
      (node (ref "R3") (pin "2") (pinfunction "2_2") (pintype "passive"))
      (node (ref "SV3") (pin "3") (pinfunction "3_3") (pintype "passive"))
    )
    (net (code "84") (name "Net-(R4-Pad2)") (class "Default")
      (node (ref "R4") (pin "2") (pinfunction "2_2") (pintype "passive"))
      (node (ref "SV4") (pin "3") (pinfunction "3_3") (pintype "passive"))
    )
    (net (code "85") (name "Net-(R5-Pad2)") (class "Default")
      (node (ref "R5") (pin "2") (pinfunction "2_2") (pintype "passive"))
      (node (ref "SV5") (pin "3") (pinfunction "3_3") (pintype "passive"))
    )
    (net (code "86") (name "Net-(R6-Pad2)") (class "Default")
      (node (ref "R6") (pin "2") (pinfunction "2_2") (pintype "passive"))
      (node (ref "SV6") (pin "3") (pinfunction "3_3") (pintype "passive"))
    )
    (net (code "87") (name "Net-(R7-Pad2)") (class "Default")
      (node (ref "R7") (pin "2") (pinfunction "2_2") (pintype "passive"))
      (node (ref "SV7") (pin "3") (pinfunction "3_3") (pintype "passive"))
    )
    (net (code "88") (name "Net-(R8-Pad2)") (class "Default")
      (node (ref "R8") (pin "2") (pinfunction "2_2") (pintype "passive"))
      (node (ref "SV8") (pin "3") (pinfunction "3_3") (pintype "passive"))
    )
    (net (code "89") (name "Net-(R9-Pad2)") (class "Default")
      (node (ref "R9") (pin "2") (pinfunction "2_2") (pintype "passive"))
      (node (ref "SV9") (pin "3") (pinfunction "3_3") (pintype "passive"))
    )
    (net (code "90") (name "Net-(R10-Pad2)") (class "Default")
      (node (ref "R10") (pin "2") (pinfunction "2_2") (pintype "passive"))
      (node (ref "SV10") (pin "3") (pinfunction "3_3") (pintype "passive"))
    )
    (net (code "91") (name "Net-(R11-Pad2)") (class "Default")
      (node (ref "R11") (pin "2") (pinfunction "2_2") (pintype "passive"))
      (node (ref "SV11") (pin "3") (pinfunction "3_3") (pintype "passive"))
    )
    (net (code "92") (name "Net-(R12-Pad2)") (class "Default")
      (node (ref "R12") (pin "2") (pinfunction "2_2") (pintype "passive"))
      (node (ref "SV12") (pin "3") (pinfunction "3_3") (pintype "passive"))
    )
    (net (code "93") (name "Net-(R13-Pad2)") (class "Default")
      (node (ref "R13") (pin "2") (pinfunction "2_2") (pintype "passive"))
      (node (ref "SV14") (pin "3") (pinfunction "3_3") (pintype "passive"))
    )
    (net (code "94") (name "Net-(R14-Pad2)") (class "Default")
      (node (ref "R14") (pin "2") (pinfunction "2_2") (pintype "passive"))
      (node (ref "SV13") (pin "3") (pinfunction "3_3") (pintype "passive"))
    )
    (net (code "95") (name "Net-(R15-Pad2)") (class "Default")
      (node (ref "R15") (pin "2") (pinfunction "2_2") (pintype "passive"))
      (node (ref "SV15") (pin "3") (pinfunction "3_3") (pintype "passive"))
    )
    (net (code "96") (name "Net-(R16-Pad2)") (class "Default")
      (node (ref "R16") (pin "2") (pinfunction "2_2") (pintype "passive"))
      (node (ref "SV16") (pin "3") (pinfunction "3_3") (pintype "passive"))
    )
    (net (code "97") (name "Net-(R17-Pad2)") (class "Default")
      (node (ref "R17") (pin "2") (pinfunction "2_2") (pintype "passive"))
      (node (ref "SV1") (pin "2") (pinfunction "2_2") (pintype "passive"))
    )
    (net (code "98") (name "Net-(R18-Pad2)") (class "Default")
      (node (ref "R18") (pin "2") (pinfunction "2_2") (pintype "passive"))
      (node (ref "SV2") (pin "2") (pinfunction "2_2") (pintype "passive"))
    )
    (net (code "99") (name "Net-(R19-Pad2)") (class "Default")
      (node (ref "R19") (pin "2") (pinfunction "2_2") (pintype "passive"))
      (node (ref "SV3") (pin "2") (pinfunction "2_2") (pintype "passive"))
    )
    (net (code "100") (name "Net-(R20-Pad2)") (class "Default")
      (node (ref "R20") (pin "2") (pinfunction "2_2") (pintype "passive"))
      (node (ref "SV4") (pin "2") (pinfunction "2_2") (pintype "passive"))
    )
    (net (code "101") (name "Net-(R21-Pad2)") (class "Default")
      (node (ref "R21") (pin "2") (pinfunction "2_2") (pintype "passive"))
      (node (ref "SV5") (pin "2") (pinfunction "2_2") (pintype "passive"))
    )
    (net (code "102") (name "Net-(R22-Pad2)") (class "Default")
      (node (ref "R22") (pin "2") (pinfunction "2_2") (pintype "passive"))
      (node (ref "SV6") (pin "2") (pinfunction "2_2") (pintype "passive"))
    )
    (net (code "103") (name "Net-(R23-Pad2)") (class "Default")
      (node (ref "R23") (pin "2") (pinfunction "2_2") (pintype "passive"))
      (node (ref "SV7") (pin "2") (pinfunction "2_2") (pintype "passive"))
    )
    (net (code "104") (name "Net-(R24-Pad2)") (class "Default")
      (node (ref "R24") (pin "2") (pinfunction "2_2") (pintype "passive"))
      (node (ref "SV8") (pin "2") (pinfunction "2_2") (pintype "passive"))
    )
    (net (code "105") (name "Net-(R25-Pad2)") (class "Default")
      (node (ref "R25") (pin "2") (pinfunction "2_2") (pintype "passive"))
      (node (ref "SV9") (pin "2") (pinfunction "2_2") (pintype "passive"))
    )
    (net (code "106") (name "Net-(R26-Pad2)") (class "Default")
      (node (ref "R26") (pin "2") (pinfunction "2_2") (pintype "passive"))
      (node (ref "SV10") (pin "2") (pinfunction "2_2") (pintype "passive"))
    )
    (net (code "107") (name "Net-(R27-Pad2)") (class "Default")
      (node (ref "R27") (pin "2") (pinfunction "2_2") (pintype "passive"))
      (node (ref "SV11") (pin "2") (pinfunction "2_2") (pintype "passive"))
    )
    (net (code "108") (name "Net-(R28-Pad2)") (class "Default")
      (node (ref "R28") (pin "2") (pinfunction "2_2") (pintype "passive"))
      (node (ref "SV12") (pin "2") (pinfunction "2_2") (pintype "passive"))
    )
    (net (code "109") (name "Net-(R29-Pad2)") (class "Default")
      (node (ref "R29") (pin "2") (pinfunction "2_2") (pintype "passive"))
      (node (ref "SV13") (pin "2") (pinfunction "2_2") (pintype "passive"))
    )
    (net (code "110") (name "Net-(R30-Pad2)") (class "Default")
      (node (ref "R30") (pin "2") (pinfunction "2_2") (pintype "passive"))
      (node (ref "SV14") (pin "2") (pinfunction "2_2") (pintype "passive"))
    )
    (net (code "111") (name "Net-(R31-Pad2)") (class "Default")
      (node (ref "R31") (pin "2") (pinfunction "2_2") (pintype "passive"))
      (node (ref "SV15") (pin "2") (pinfunction "2_2") (pintype "passive"))
    )
    (net (code "112") (name "Net-(R32-Pad2)") (class "Default")
      (node (ref "R32") (pin "2") (pinfunction "2_2") (pintype "passive"))
      (node (ref "SV16") (pin "2") (pinfunction "2_2") (pintype "passive"))
    )
    (net (code "113") (name "Net-(R33-Pad2)") (class "Default")
      (node (ref "R33") (pin "2") (pinfunction "2_2") (pintype "passive"))
      (node (ref "SV9") (pin "1") (pinfunction "1_1") (pintype "passive"))
    )
    (net (code "114") (name "Net-(R34-Pad2)") (class "Default")
      (node (ref "R34") (pin "2") (pinfunction "2_2") (pintype "passive"))
      (node (ref "SV10") (pin "1") (pinfunction "1_1") (pintype "passive"))
    )
    (net (code "115") (name "Net-(R35-Pad2)") (class "Default")
      (node (ref "R35") (pin "2") (pinfunction "2_2") (pintype "passive"))
      (node (ref "SV11") (pin "1") (pinfunction "1_1") (pintype "passive"))
    )
    (net (code "116") (name "Net-(R36-Pad2)") (class "Default")
      (node (ref "R36") (pin "2") (pinfunction "2_2") (pintype "passive"))
      (node (ref "SV12") (pin "1") (pinfunction "1_1") (pintype "passive"))
    )
    (net (code "117") (name "Net-(R37-Pad2)") (class "Default")
      (node (ref "R37") (pin "2") (pinfunction "2_2") (pintype "passive"))
      (node (ref "SV13") (pin "1") (pinfunction "1_1") (pintype "passive"))
    )
    (net (code "118") (name "Net-(R38-Pad2)") (class "Default")
      (node (ref "R38") (pin "2") (pinfunction "2_2") (pintype "passive"))
      (node (ref "SV14") (pin "1") (pinfunction "1_1") (pintype "passive"))
    )
    (net (code "119") (name "Net-(R39-Pad2)") (class "Default")
      (node (ref "R39") (pin "2") (pinfunction "2_2") (pintype "passive"))
      (node (ref "SV15") (pin "1") (pinfunction "1_1") (pintype "passive"))
    )
    (net (code "120") (name "Net-(R40-Pad2)") (class "Default")
      (node (ref "R40") (pin "2") (pinfunction "2_2") (pintype "passive"))
      (node (ref "SV16") (pin "1") (pinfunction "1_1") (pintype "passive"))
    )
    (net (code "121") (name "Net-(R41-Pad2)") (class "Default")
      (node (ref "R41") (pin "2") (pinfunction "2_2") (pintype "passive"))
      (node (ref "SV1") (pin "1") (pinfunction "1_1") (pintype "passive"))
    )
    (net (code "122") (name "Net-(R42-Pad2)") (class "Default")
      (node (ref "R42") (pin "2") (pinfunction "2_2") (pintype "passive"))
      (node (ref "SV2") (pin "1") (pinfunction "1_1") (pintype "passive"))
    )
    (net (code "123") (name "Net-(R43-Pad2)") (class "Default")
      (node (ref "R43") (pin "2") (pinfunction "2_2") (pintype "passive"))
      (node (ref "SV3") (pin "1") (pinfunction "1_1") (pintype "passive"))
    )
    (net (code "124") (name "Net-(R44-Pad2)") (class "Default")
      (node (ref "R44") (pin "2") (pinfunction "2_2") (pintype "passive"))
      (node (ref "SV4") (pin "1") (pinfunction "1_1") (pintype "passive"))
    )
    (net (code "125") (name "Net-(R45-Pad2)") (class "Default")
      (node (ref "R45") (pin "2") (pinfunction "2_2") (pintype "passive"))
      (node (ref "SV5") (pin "1") (pinfunction "1_1") (pintype "passive"))
    )
    (net (code "126") (name "Net-(R46-Pad2)") (class "Default")
      (node (ref "R46") (pin "2") (pinfunction "2_2") (pintype "passive"))
      (node (ref "SV6") (pin "1") (pinfunction "1_1") (pintype "passive"))
    )
    (net (code "127") (name "Net-(R47-Pad2)") (class "Default")
      (node (ref "R47") (pin "2") (pinfunction "2_2") (pintype "passive"))
      (node (ref "SV7") (pin "1") (pinfunction "1_1") (pintype "passive"))
    )
    (net (code "128") (name "Net-(R48-Pad2)") (class "Default")
      (node (ref "R48") (pin "2") (pinfunction "2_2") (pintype "passive"))
      (node (ref "SV8") (pin "1") (pinfunction "1_1") (pintype "passive"))
    )
    (net (code "129") (name "VCC") (class "Default")
      (node (ref "C1") (pin "1") (pinfunction "1_1") (pintype "passive"))
      (node (ref "C2") (pin "1") (pinfunction "1_1") (pintype "passive"))
      (node (ref "C3") (pin "1") (pinfunction "1_1") (pintype "passive"))
      (node (ref "C4") (pin "1") (pinfunction "1_1") (pintype "passive"))
      (node (ref "C5") (pin "1") (pinfunction "1_1") (pintype "passive"))
      (node (ref "C6") (pin "1") (pinfunction "1_1") (pintype "passive"))
      (node (ref "C7") (pin "1") (pinfunction "1_1") (pintype "passive"))
      (node (ref "IC1") (pin "20") (pinfunction "VCC_20") (pintype "power_in"))
      (node (ref "IC2") (pin "20") (pinfunction "VCC_20") (pintype "power_in"))
      (node (ref "IC3") (pin "20") (pinfunction "VCC_20") (pintype "power_in"))
      (node (ref "IC4") (pin "20") (pinfunction "VCC_20") (pintype "power_in"))
      (node (ref "IC5") (pin "20") (pinfunction "VCC_20") (pintype "power_in"))
      (node (ref "IC6") (pin "20") (pinfunction "VCC_20") (pintype "power_in"))
      (node (ref "IC7") (pin "16") (pinfunction "VCC_16") (pintype "power_in"))
      (node (ref "IC7") (pin "6") (pinfunction "G1_6") (pintype "input"))
      (node (ref "R53") (pin "1") (pinfunction "1_1") (pintype "passive"))
      (node (ref "R54") (pin "1") (pinfunction "1_1") (pintype "passive"))
      (node (ref "R55") (pin "1") (pinfunction "1_1") (pintype "passive"))
      (node (ref "R56") (pin "1") (pinfunction "1_1") (pintype "passive"))
      (node (ref "U$1") (pin "5V") (pinfunction "5.5V_5V") (pintype "bidirectional"))
    )
    (net (code "130") (name "unconnected-(IC7A-Y6-Pad9)") (class "Default")
      (node (ref "IC7") (pin "9") (pinfunction "Y6_9") (pintype "output"))
    )
    (net (code "131") (name "unconnected-(IC7A-Y7-Pad7)") (class "Default")
      (node (ref "IC7") (pin "7") (pinfunction "Y7_7") (pintype "output"))
    )
    (net (code "132") (name "unconnected-(U$1-Pad3.3V)") (class "Default")
      (node (ref "U$1") (pin "3.3V") (pinfunction "3.3V_3.3V") (pintype "bidirectional"))
    )
    (net (code "133") (name "unconnected-(U$1-PadA3)") (class "Default")
      (node (ref "U$1") (pin "A3") (pinfunction "A3_A3") (pintype "bidirectional"))
    )
    (net (code "134") (name "unconnected-(U$1-PadA4)") (class "Default")
      (node (ref "U$1") (pin "A4") (pinfunction "A4_A4") (pintype "bidirectional"))
    )
    (net (code "135") (name "unconnected-(U$1-PadA5)") (class "Default")
      (node (ref "U$1") (pin "A5") (pinfunction "A5_A5") (pintype "bidirectional"))
    )
    (net (code "136") (name "unconnected-(U$1-PadA6)") (class "Default")
      (node (ref "U$1") (pin "A6") (pinfunction "A6_A6") (pintype "bidirectional"))
    )
    (net (code "137") (name "unconnected-(U$1-PadA7)") (class "Default")
      (node (ref "U$1") (pin "A7") (pinfunction "A7_A7") (pintype "bidirectional"))
    )
    (net (code "138") (name "unconnected-(U$1-PadAREF)") (class "Default")
      (node (ref "U$1") (pin "AREF") (pinfunction "AREF_AREF") (pintype "bidirectional"))
    )
    (net (code "139") (name "unconnected-(U$1-PadD13)") (class "Default")
      (node (ref "U$1") (pin "D13") (pinfunction "D13_D13") (pintype "bidirectional"))
    )
    (net (code "140") (name "unconnected-(U$1-PadICSP1)") (class "Default")
      (node (ref "U$1") (pin "ICSP1") (pinfunction "ICSP1_ICSP1") (pintype "bidirectional"))
    )
    (net (code "141") (name "unconnected-(U$1-PadICSP2)") (class "Default")
      (node (ref "U$1") (pin "ICSP2") (pinfunction "ICSP2_ICSP2") (pintype "bidirectional"))
    )
    (net (code "142") (name "unconnected-(U$1-PadICSP3)") (class "Default")
      (node (ref "U$1") (pin "ICSP3") (pinfunction "ICSP3_ICSP3") (pintype "bidirectional"))
    )
    (net (code "143") (name "unconnected-(U$1-PadICSP4)") (class "Default")
      (node (ref "U$1") (pin "ICSP4") (pinfunction "ICSP4_ICSP4") (pintype "bidirectional"))
    )
    (net (code "144") (name "unconnected-(U$1-PadICSP5)") (class "Default")
      (node (ref "U$1") (pin "ICSP5") (pinfunction "ICSP5_ICSP5") (pintype "bidirectional"))
    )
    (net (code "145") (name "unconnected-(U$1-PadICSP6)") (class "Default")
      (node (ref "U$1") (pin "ICSP6") (pinfunction "ICSP6_ICSP6") (pintype "bidirectional"))
    )
    (net (code "146") (name "unconnected-(U$1-PadRAW)") (class "Default")
      (node (ref "U$1") (pin "RAW") (pinfunction "RAW_RAW") (pintype "bidirectional"))
    )
    (net (code "147") (name "unconnected-(U$1-PadRST)") (class "Default")
      (node (ref "U$1") (pin "RST") (pinfunction "RST_RST") (pintype "bidirectional"))
    )
    (net (code "148") (name "unconnected-(U$1-PadRST1)") (class "Default")
      (node (ref "U$1") (pin "RST1") (pinfunction "RST1_RST1") (pintype "bidirectional"))
    )
  )
)
